# roadkill.net
KiCad netlist of a schematic drawn in EAGLE
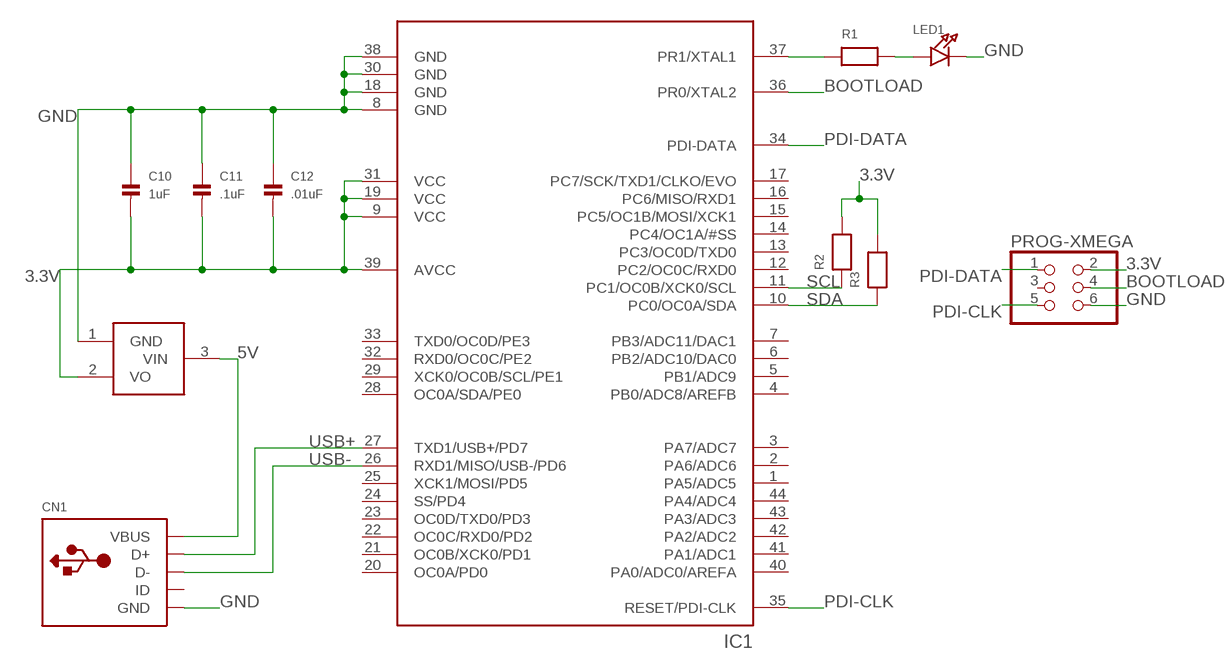
[diagram p0: schematic, sheet 1]
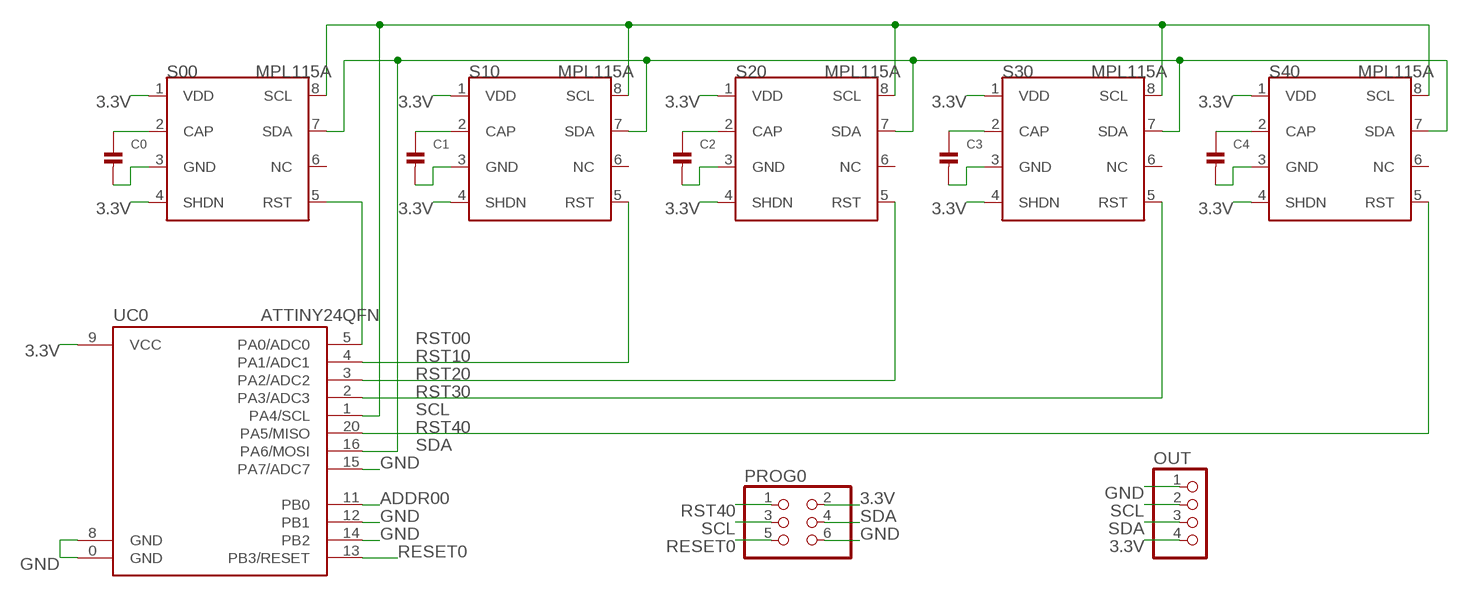
[diagram p1: schematic, sheet 2]
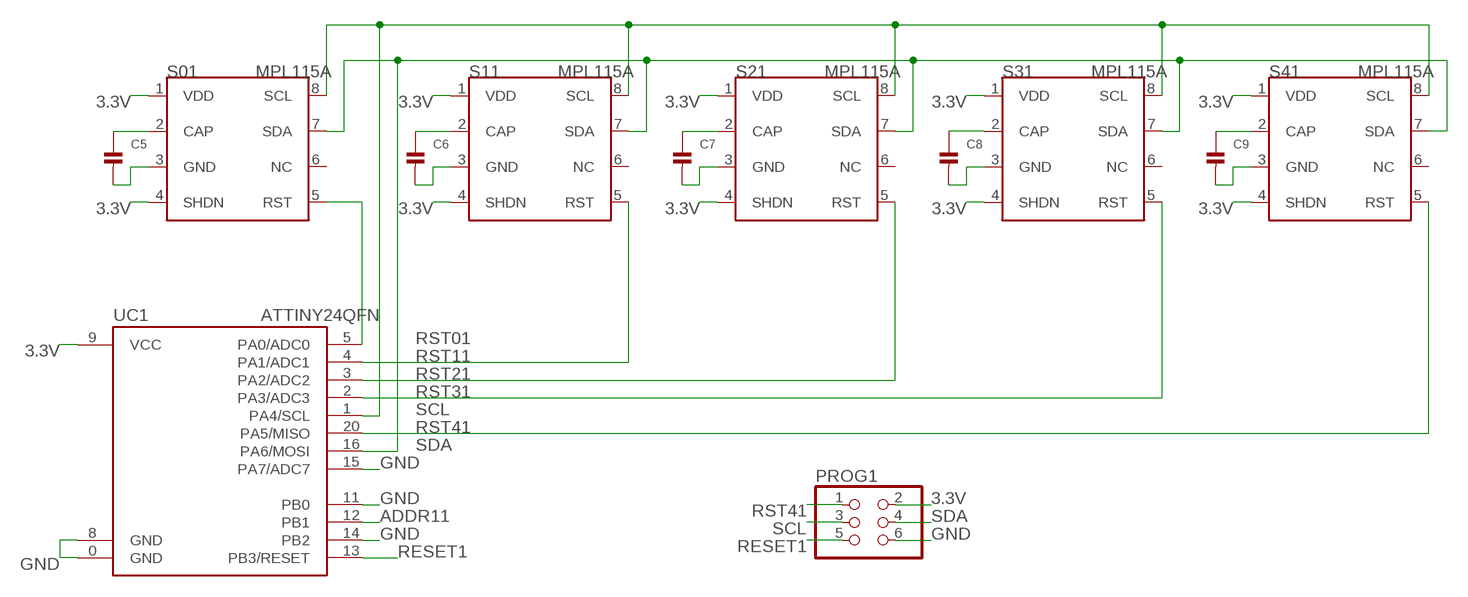
[diagram p2: schematic, sheet 3]
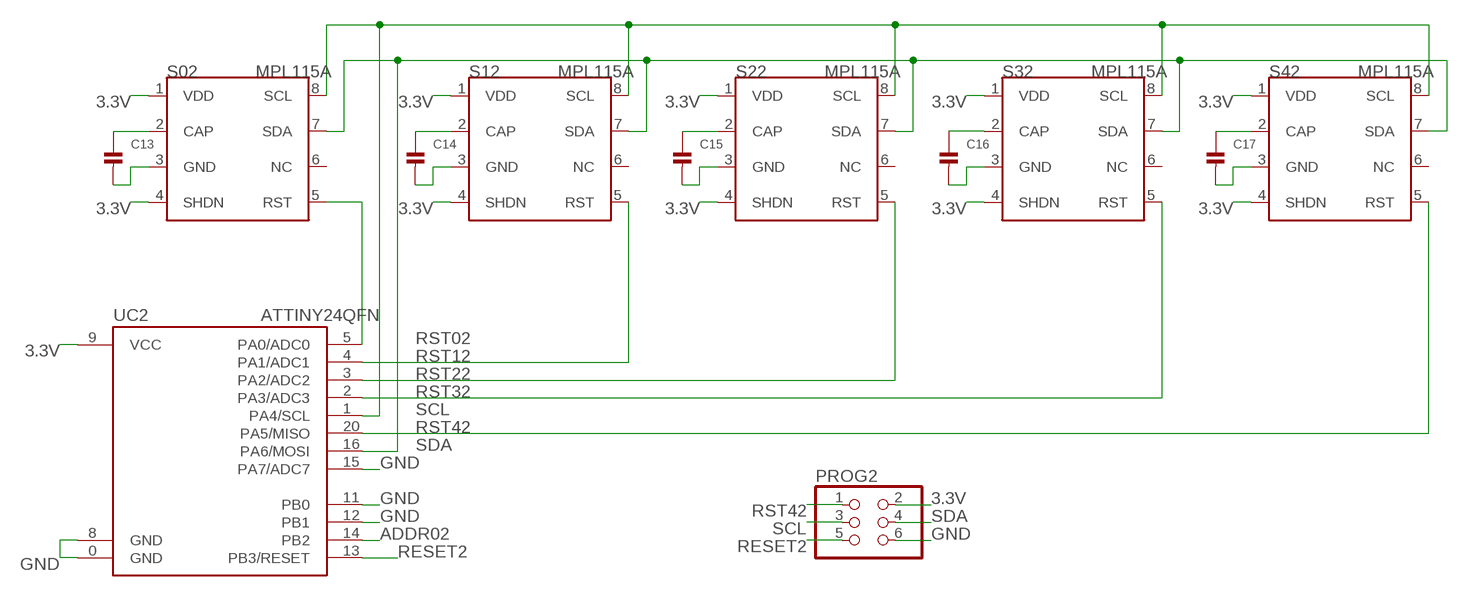
[diagram p3: schematic, sheet 4]
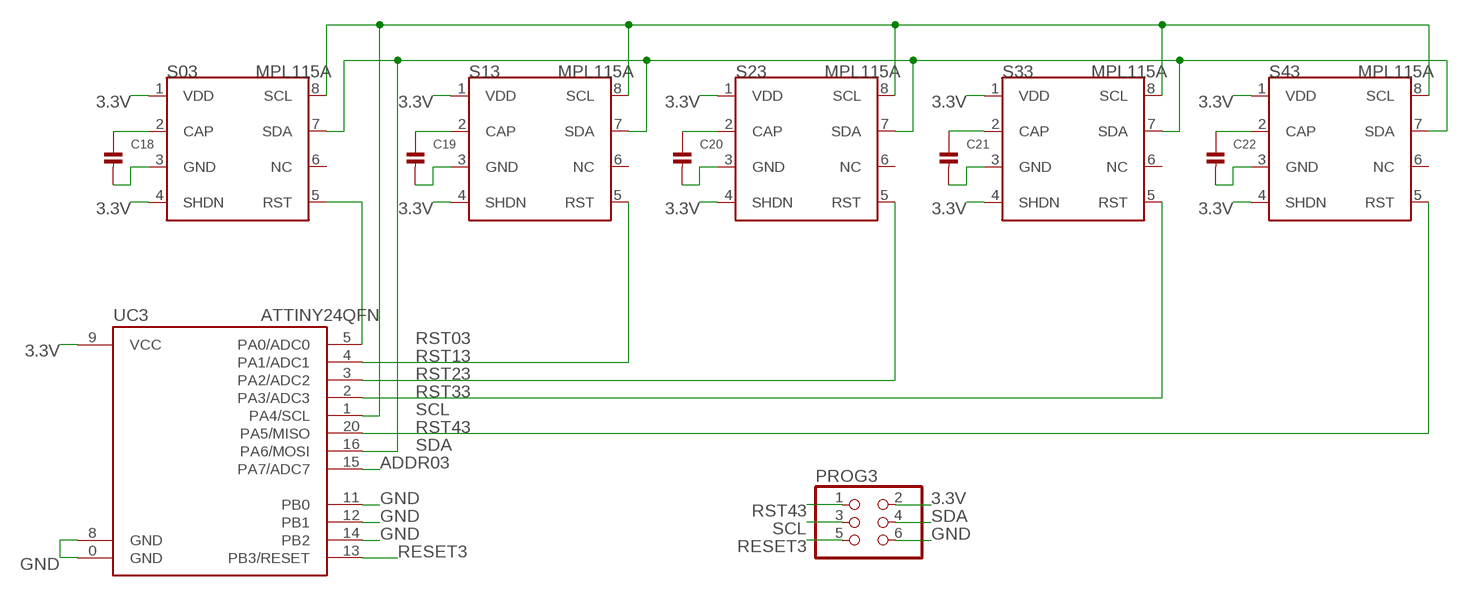
[diagram p4: schematic, sheet 5]

(export (version "E")
  (design (tool "Eeschema 10.0.6"))
  (components
    (comp (ref "C0")
      (value "CAP_CERAMIC0603")
      (footprint "eagle-import:0603")
      (libsource (lib "eagle-import") (part "CAP_CERAMIC0603"))
    )
    (comp (ref "C1")
      (value "CAP_CERAMIC0603")
      (footprint "eagle-import:0603")
      (libsource (lib "eagle-import") (part "CAP_CERAMIC0603"))
    )
    (comp (ref "C2")
      (value "CAP_CERAMIC0603")
      (footprint "eagle-import:0603")
      (libsource (lib "eagle-import") (part "CAP_CERAMIC0603"))
    )
    (comp (ref "C3")
      (value "CAP_CERAMIC0603")
      (footprint "eagle-import:0603")
      (libsource (lib "eagle-import") (part "CAP_CERAMIC0603"))
    )
    (comp (ref "C4")
      (value "CAP_CERAMIC0603")
      (footprint "eagle-import:0603")
      (libsource (lib "eagle-import") (part "CAP_CERAMIC0603"))
    )
    (comp (ref "OUT")
      (value "HEADER-1X4")
      (footprint "eagle-import:1X04_OVAL")
      (libsource (lib "eagle-import") (part "HEADER-1X4"))
    )
    (comp (ref "PROG0")
      (value "HEADER-2X3")
      (footprint "eagle-import:2X03")
      (libsource (lib "eagle-import") (part "HEADER-2X3"))
    )
    (comp (ref "S00")
      (value "MPL115A")
      (footprint "eagle-import:LGA-8")
      (libsource (lib "eagle-import") (part "MPL115A"))
    )
    (comp (ref "S10")
      (value "MPL115A")
      (footprint "eagle-import:LGA-8")
      (libsource (lib "eagle-import") (part "MPL115A"))
    )
    (comp (ref "S20")
      (value "MPL115A")
      (footprint "eagle-import:LGA-8")
      (libsource (lib "eagle-import") (part "MPL115A"))
    )
    (comp (ref "S30")
      (value "MPL115A")
      (footprint "eagle-import:LGA-8")
      (libsource (lib "eagle-import") (part "MPL115A"))
    )
    (comp (ref "S40")
      (value "MPL115A")
      (footprint "eagle-import:LGA-8")
      (libsource (lib "eagle-import") (part "MPL115A"))
    )
    (comp (ref "UC0")
      (value "ATTINY24QFN")
      (footprint "eagle-import:QFN20")
      (libsource (lib "eagle-import") (part "ATTINY24QFN"))
    )
    (comp (ref "C18")
      (value "CAP_CERAMIC0603")
      (footprint "eagle-import:0603")
      (libsource (lib "eagle-import") (part "CAP_CERAMIC0603"))
    )
    (comp (ref "C19")
      (value "CAP_CERAMIC0603")
      (footprint "eagle-import:0603")
      (libsource (lib "eagle-import") (part "CAP_CERAMIC0603"))
    )
    (comp (ref "C20")
      (value "CAP_CERAMIC0603")
      (footprint "eagle-import:0603")
      (libsource (lib "eagle-import") (part "CAP_CERAMIC0603"))
    )
    (comp (ref "C21")
      (value "CAP_CERAMIC0603")
      (footprint "eagle-import:0603")
      (libsource (lib "eagle-import") (part "CAP_CERAMIC0603"))
    )
    (comp (ref "C22")
      (value "CAP_CERAMIC0603")
      (footprint "eagle-import:0603")
      (libsource (lib "eagle-import") (part "CAP_CERAMIC0603"))
    )
    (comp (ref "PROG3")
      (value "HEADER-2X3")
      (footprint "eagle-import:2X03")
      (libsource (lib "eagle-import") (part "HEADER-2X3"))
    )
    (comp (ref "S03")
      (value "MPL115A")
      (footprint "eagle-import:LGA-8")
      (libsource (lib "eagle-import") (part "MPL115A"))
    )
    (comp (ref "S13")
      (value "MPL115A")
      (footprint "eagle-import:LGA-8")
      (libsource (lib "eagle-import") (part "MPL115A"))
    )
    (comp (ref "S23")
      (value "MPL115A")
      (footprint "eagle-import:LGA-8")
      (libsource (lib "eagle-import") (part "MPL115A"))
    )
    (comp (ref "S33")
      (value "MPL115A")
      (footprint "eagle-import:LGA-8")
      (libsource (lib "eagle-import") (part "MPL115A"))
    )
    (comp (ref "S43")
      (value "MPL115A")
      (footprint "eagle-import:LGA-8")
      (libsource (lib "eagle-import") (part "MPL115A"))
    )
    (comp (ref "UC3")
      (value "ATTINY24QFN")
      (footprint "eagle-import:QFN20")
      (libsource (lib "eagle-import") (part "ATTINY24QFN"))
    )
    (comp (ref "C5")
      (value "CAP_CERAMIC0603")
      (footprint "eagle-import:0603")
      (libsource (lib "eagle-import") (part "CAP_CERAMIC0603"))
    )
    (comp (ref "C6")
      (value "CAP_CERAMIC0603")
      (footprint "eagle-import:0603")
      (libsource (lib "eagle-import") (part "CAP_CERAMIC0603"))
    )
    (comp (ref "C7")
      (value "CAP_CERAMIC0603")
      (footprint "eagle-import:0603")
      (libsource (lib "eagle-import") (part "CAP_CERAMIC0603"))
    )
    (comp (ref "C8")
      (value "CAP_CERAMIC0603")
      (footprint "eagle-import:0603")
      (libsource (lib "eagle-import") (part "CAP_CERAMIC0603"))
    )
    (comp (ref "C9")
      (value "CAP_CERAMIC0603")
      (footprint "eagle-import:0603")
      (libsource (lib "eagle-import") (part "CAP_CERAMIC0603"))
    )
    (comp (ref "PROG1")
      (value "HEADER-2X3")
      (footprint "eagle-import:2X03")
      (libsource (lib "eagle-import") (part "HEADER-2X3"))
    )
    (comp (ref "S01")
      (value "MPL115A")
      (footprint "eagle-import:LGA-8")
      (libsource (lib "eagle-import") (part "MPL115A"))
    )
    (comp (ref "S11")
      (value "MPL115A")
      (footprint "eagle-import:LGA-8")
      (libsource (lib "eagle-import") (part "MPL115A"))
    )
    (comp (ref "S21")
      (value "MPL115A")
      (footprint "eagle-import:LGA-8")
      (libsource (lib "eagle-import") (part "MPL115A"))
    )
    (comp (ref "S31")
      (value "MPL115A")
      (footprint "eagle-import:LGA-8")
      (libsource (lib "eagle-import") (part "MPL115A"))
    )
    (comp (ref "S41")
      (value "MPL115A")
      (footprint "eagle-import:LGA-8")
      (libsource (lib "eagle-import") (part "MPL115A"))
    )
    (comp (ref "UC1")
      (value "ATTINY24QFN")
      (footprint "eagle-import:QFN20")
      (libsource (lib "eagle-import") (part "ATTINY24QFN"))
    )
    (comp (ref "C13")
      (value "CAP_CERAMIC0603")
      (footprint "eagle-import:0603")
      (libsource (lib "eagle-import") (part "CAP_CERAMIC0603"))
    )
    (comp (ref "C14")
      (value "CAP_CERAMIC0603")
      (footprint "eagle-import:0603")
      (libsource (lib "eagle-import") (part "CAP_CERAMIC0603"))
    )
    (comp (ref "C15")
      (value "CAP_CERAMIC0603")
      (footprint "eagle-import:0603")
      (libsource (lib "eagle-import") (part "CAP_CERAMIC0603"))
    )
    (comp (ref "C16")
      (value "CAP_CERAMIC0603")
      (footprint "eagle-import:0603")
      (libsource (lib "eagle-import") (part "CAP_CERAMIC0603"))
    )
    (comp (ref "C17")
      (value "CAP_CERAMIC0603")
      (footprint "eagle-import:0603")
      (libsource (lib "eagle-import") (part "CAP_CERAMIC0603"))
    )
    (comp (ref "PROG2")
      (value "HEADER-2X3")
      (footprint "eagle-import:2X03")
      (libsource (lib "eagle-import") (part "HEADER-2X3"))
    )
    (comp (ref "S02")
      (value "MPL115A")
      (footprint "eagle-import:LGA-8")
      (libsource (lib "eagle-import") (part "MPL115A"))
    )
    (comp (ref "S12")
      (value "MPL115A")
      (footprint "eagle-import:LGA-8")
      (libsource (lib "eagle-import") (part "MPL115A"))
    )
    (comp (ref "S22")
      (value "MPL115A")
      (footprint "eagle-import:LGA-8")
      (libsource (lib "eagle-import") (part "MPL115A"))
    )
    (comp (ref "S32")
      (value "MPL115A")
      (footprint "eagle-import:LGA-8")
      (libsource (lib "eagle-import") (part "MPL115A"))
    )
    (comp (ref "S42")
      (value "MPL115A")
      (footprint "eagle-import:LGA-8")
      (libsource (lib "eagle-import") (part "MPL115A"))
    )
    (comp (ref "UC2")
      (value "ATTINY24QFN")
      (footprint "eagle-import:QFN20")
      (libsource (lib "eagle-import") (part "ATTINY24QFN"))
    )
    (comp (ref "3.3V")
      (value "VREG")
      (footprint "eagle-import:SOT23-3")
      (libsource (lib "eagle-import") (part "VREG"))
    )
    (comp (ref "C10")
      (value "1uF")
      (footprint "eagle-import:0603")
      (libsource (lib "eagle-import") (part "CAP_CERAMIC0603"))
    )
    (comp (ref "C11")
      (value ".1uF")
      (footprint "eagle-import:0603")
      (libsource (lib "eagle-import") (part "CAP_CERAMIC0603"))
    )
    (comp (ref "C12")
      (value ".01uF")
      (footprint "eagle-import:0603")
      (libsource (lib "eagle-import") (part "CAP_CERAMIC0603"))
    )
    (comp (ref "CN1")
      (value "USBMINIB")
      (footprint "eagle-import:USB-MINIB")
      (libsource (lib "eagle-import") (part "USBMINIB"))
    )
    (comp (ref "IC1")
      (value "ATXMEGAXXA4U")
      (footprint "eagle-import:TQFP-44")
      (libsource (lib "eagle-import") (part "ATXMEGAXXA4U"))
    )
    (comp (ref "LED1")
      (value "LED0603")
      (footprint "eagle-import:CHIPLED_0603")
      (libsource (lib "eagle-import") (part "LED0603"))
    )
    (comp (ref "PROG-XMEGA")
      (value "HEADER-2X3")
      (footprint "eagle-import:2X03")
      (libsource (lib "eagle-import") (part "HEADER-2X3"))
    )
    (comp (ref "R1")
      (value "RESISTOR0603")
      (footprint "eagle-import:0603")
      (libsource (lib "eagle-import") (part "RESISTOR0603"))
    )
    (comp (ref "R2")
      (value "RESISTOR0603")
      (footprint "eagle-import:0603")
      (libsource (lib "eagle-import") (part "RESISTOR0603"))
    )
    (comp (ref "R3")
      (value "RESISTOR0603")
      (footprint "eagle-import:0603")
      (libsource (lib "eagle-import") (part "RESISTOR0603"))
    )
  )
  (nets
    (net (code "1") (name "3.3V") (class "Default")
      (node (ref "3.3V") (pin "2") (pinfunction "VO_2") (pintype "bidirectional"))
      (node (ref "C10") (pin "2") (pinfunction "P$2_2") (pintype "passive"))
      (node (ref "C11") (pin "2") (pinfunction "P$2_2") (pintype "passive"))
      (node (ref "C12") (pin "2") (pinfunction "P$2_2") (pintype "passive"))
      (node (ref "IC1") (pin "19") (pinfunction "VCC_19") (pintype "power_in"))
      (node (ref "IC1") (pin "31") (pinfunction "VCC_31") (pintype "power_in"))
      (node (ref "IC1") (pin "39") (pinfunction "AVCC_39") (pintype "power_in"))
      (node (ref "IC1") (pin "9") (pinfunction "VCC_9") (pintype "power_in"))
      (node (ref "OUT") (pin "4") (pinfunction "4_4") (pintype "passive"))
      (node (ref "PROG-XMEGA") (pin "2") (pinfunction "2_2") (pintype "passive"))
      (node (ref "PROG0") (pin "2") (pinfunction "2_2") (pintype "passive"))
      (node (ref "PROG1") (pin "2") (pinfunction "2_2") (pintype "passive"))
      (node (ref "PROG2") (pin "2") (pinfunction "2_2") (pintype "passive"))
      (node (ref "PROG3") (pin "2") (pinfunction "2_2") (pintype "passive"))
      (node (ref "R2") (pin "2") (pinfunction "2_2") (pintype "passive"))
      (node (ref "R3") (pin "2") (pinfunction "2_2") (pintype "passive"))
      (node (ref "S00") (pin "1") (pinfunction "VDD_1") (pintype "bidirectional"))
      (node (ref "S00") (pin "4") (pinfunction "SHDN_4") (pintype "bidirectional"))
      (node (ref "S01") (pin "1") (pinfunction "VDD_1") (pintype "bidirectional"))
      (node (ref "S01") (pin "4") (pinfunction "SHDN_4") (pintype "bidirectional"))
      (node (ref "S02") (pin "1") (pinfunction "VDD_1") (pintype "bidirectional"))
      (node (ref "S02") (pin "4") (pinfunction "SHDN_4") (pintype "bidirectional"))
      (node (ref "S03") (pin "1") (pinfunction "VDD_1") (pintype "bidirectional"))
      (node (ref "S03") (pin "4") (pinfunction "SHDN_4") (pintype "bidirectional"))
      (node (ref "S10") (pin "1") (pinfunction "VDD_1") (pintype "bidirectional"))
      (node (ref "S10") (pin "4") (pinfunction "SHDN_4") (pintype "bidirectional"))
      (node (ref "S11") (pin "1") (pinfunction "VDD_1") (pintype "bidirectional"))
      (node (ref "S11") (pin "4") (pinfunction "SHDN_4") (pintype "bidirectional"))
      (node (ref "S12") (pin "1") (pinfunction "VDD_1") (pintype "bidirectional"))
      (node (ref "S12") (pin "4") (pinfunction "SHDN_4") (pintype "bidirectional"))
      (node (ref "S13") (pin "1") (pinfunction "VDD_1") (pintype "bidirectional"))
      (node (ref "S13") (pin "4") (pinfunction "SHDN_4") (pintype "bidirectional"))
      (node (ref "S20") (pin "1") (pinfunction "VDD_1") (pintype "bidirectional"))
      (node (ref "S20") (pin "4") (pinfunction "SHDN_4") (pintype "bidirectional"))
      (node (ref "S21") (pin "1") (pinfunction "VDD_1") (pintype "bidirectional"))
      (node (ref "S21") (pin "4") (pinfunction "SHDN_4") (pintype "bidirectional"))
      (node (ref "S22") (pin "1") (pinfunction "VDD_1") (pintype "bidirectional"))
      (node (ref "S22") (pin "4") (pinfunction "SHDN_4") (pintype "bidirectional"))
      (node (ref "S23") (pin "1") (pinfunction "VDD_1") (pintype "bidirectional"))
      (node (ref "S23") (pin "4") (pinfunction "SHDN_4") (pintype "bidirectional"))
      (node (ref "S30") (pin "1") (pinfunction "VDD_1") (pintype "bidirectional"))
      (node (ref "S30") (pin "4") (pinfunction "SHDN_4") (pintype "bidirectional"))
      (node (ref "S31") (pin "1") (pinfunction "VDD_1") (pintype "bidirectional"))
      (node (ref "S31") (pin "4") (pinfunction "SHDN_4") (pintype "bidirectional"))
      (node (ref "S32") (pin "1") (pinfunction "VDD_1") (pintype "bidirectional"))
      (node (ref "S32") (pin "4") (pinfunction "SHDN_4") (pintype "bidirectional"))
      (node (ref "S33") (pin "1") (pinfunction "VDD_1") (pintype "bidirectional"))
      (node (ref "S33") (pin "4") (pinfunction "SHDN_4") (pintype "bidirectional"))
      (node (ref "S40") (pin "1") (pinfunction "VDD_1") (pintype "bidirectional"))
      (node (ref "S40") (pin "4") (pinfunction "SHDN_4") (pintype "bidirectional"))
      (node (ref "S41") (pin "1") (pinfunction "VDD_1") (pintype "bidirectional"))
      (node (ref "S41") (pin "4") (pinfunction "SHDN_4") (pintype "bidirectional"))
      (node (ref "S42") (pin "1") (pinfunction "VDD_1") (pintype "bidirectional"))
      (node (ref "S42") (pin "4") (pinfunction "SHDN_4") (pintype "bidirectional"))
      (node (ref "S43") (pin "1") (pinfunction "VDD_1") (pintype "bidirectional"))
      (node (ref "S43") (pin "4") (pinfunction "SHDN_4") (pintype "bidirectional"))
      (node (ref "UC0") (pin "9") (pinfunction "VCC_9") (pintype "bidirectional"))
      (node (ref "UC1") (pin "9") (pinfunction "VCC_9") (pintype "bidirectional"))
      (node (ref "UC2") (pin "9") (pinfunction "VCC_9") (pintype "bidirectional"))
      (node (ref "UC3") (pin "9") (pinfunction "VCC_9") (pintype "bidirectional"))
    )
    (net (code "2") (name "5V") (class "Default")
      (node (ref "3.3V") (pin "3") (pinfunction "VIN_3") (pintype "bidirectional"))
      (node (ref "CN1") (pin "VBUS") (pinfunction "VBUS_VBUS") (pintype "power_in"))
    )
    (net (code "3") (name "ADDR00") (class "Default")
      (node (ref "UC0") (pin "11") (pinfunction "PB0_11") (pintype "bidirectional"))
    )
    (net (code "4") (name "ADDR02") (class "Default")
      (node (ref "UC2") (pin "14") (pinfunction "PB2_14") (pintype "bidirectional"))
    )
    (net (code "5") (name "ADDR03") (class "Default")
      (node (ref "UC3") (pin "15") (pinfunction "PA7/ADC7_15") (pintype "bidirectional"))
    )
    (net (code "6") (name "ADDR11") (class "Default")
      (node (ref "UC1") (pin "12") (pinfunction "PB1_12") (pintype "bidirectional"))
    )
    (net (code "7") (name "BOOTLOAD") (class "Default")
      (node (ref "IC1") (pin "36") (pinfunction "PR0/XTAL2_36") (pintype "bidirectional"))
      (node (ref "PROG-XMEGA") (pin "4") (pinfunction "4_4") (pintype "passive"))
    )
    (net (code "8") (name "GND") (class "Default")
      (node (ref "3.3V") (pin "1") (pinfunction "GND_1") (pintype "bidirectional"))
      (node (ref "C0") (pin "2") (pinfunction "P$2_2") (pintype "passive"))
      (node (ref "C1") (pin "2") (pinfunction "P$2_2") (pintype "passive"))
      (node (ref "C10") (pin "1") (pinfunction "P$1_1") (pintype "passive"))
      (node (ref "C11") (pin "1") (pinfunction "P$1_1") (pintype "passive"))
      (node (ref "C12") (pin "1") (pinfunction "P$1_1") (pintype "passive"))
      (node (ref "C13") (pin "2") (pinfunction "P$2_2") (pintype "passive"))
      (node (ref "C14") (pin "2") (pinfunction "P$2_2") (pintype "passive"))
      (node (ref "C15") (pin "2") (pinfunction "P$2_2") (pintype "passive"))
      (node (ref "C16") (pin "2") (pinfunction "P$2_2") (pintype "passive"))
      (node (ref "C17") (pin "2") (pinfunction "P$2_2") (pintype "passive"))
      (node (ref "C18") (pin "2") (pinfunction "P$2_2") (pintype "passive"))
      (node (ref "C19") (pin "2") (pinfunction "P$2_2") (pintype "passive"))
      (node (ref "C2") (pin "2") (pinfunction "P$2_2") (pintype "passive"))
      (node (ref "C20") (pin "2") (pinfunction "P$2_2") (pintype "passive"))
      (node (ref "C21") (pin "2") (pinfunction "P$2_2") (pintype "passive"))
      (node (ref "C22") (pin "2") (pinfunction "P$2_2") (pintype "passive"))
      (node (ref "C3") (pin "2") (pinfunction "P$2_2") (pintype "passive"))
      (node (ref "C4") (pin "2") (pinfunction "P$2_2") (pintype "passive"))
      (node (ref "C5") (pin "2") (pinfunction "P$2_2") (pintype "passive"))
      (node (ref "C6") (pin "2") (pinfunction "P$2_2") (pintype "passive"))
      (node (ref "C7") (pin "2") (pinfunction "P$2_2") (pintype "passive"))
      (node (ref "C8") (pin "2") (pinfunction "P$2_2") (pintype "passive"))
      (node (ref "C9") (pin "2") (pinfunction "P$2_2") (pintype "passive"))
      (node (ref "CN1") (pin "GND") (pinfunction "GND_GND") (pintype "power_in"))
      (node (ref "IC1") (pin "18") (pinfunction "GND_18") (pintype "power_in"))
      (node (ref "IC1") (pin "30") (pinfunction "GND_30") (pintype "power_in"))
      (node (ref "IC1") (pin "38") (pinfunction "GND_38") (pintype "power_in"))
      (node (ref "IC1") (pin "8") (pinfunction "GND_8") (pintype "power_in"))
      (node (ref "LED1") (pin "C") (pinfunction "C_C") (pintype "passive"))
      (node (ref "OUT") (pin "1") (pinfunction "1_1") (pintype "passive"))
      (node (ref "PROG-XMEGA") (pin "6") (pinfunction "6_6") (pintype "passive"))
      (node (ref "PROG0") (pin "6") (pinfunction "6_6") (pintype "passive"))
      (node (ref "PROG1") (pin "6") (pinfunction "6_6") (pintype "passive"))
      (node (ref "PROG2") (pin "6") (pinfunction "6_6") (pintype "passive"))
      (node (ref "PROG3") (pin "6") (pinfunction "6_6") (pintype "passive"))
      (node (ref "S00") (pin "3") (pinfunction "GND_3") (pintype "bidirectional"))
      (node (ref "S01") (pin "3") (pinfunction "GND_3") (pintype "bidirectional"))
      (node (ref "S02") (pin "3") (pinfunction "GND_3") (pintype "bidirectional"))
      (node (ref "S03") (pin "3") (pinfunction "GND_3") (pintype "bidirectional"))
      (node (ref "S10") (pin "3") (pinfunction "GND_3") (pintype "bidirectional"))
      (node (ref "S11") (pin "3") (pinfunction "GND_3") (pintype "bidirectional"))
      (node (ref "S12") (pin "3") (pinfunction "GND_3") (pintype "bidirectional"))
      (node (ref "S13") (pin "3") (pinfunction "GND_3") (pintype "bidirectional"))
      (node (ref "S20") (pin "3") (pinfunction "GND_3") (pintype "bidirectional"))
      (node (ref "S21") (pin "3") (pinfunction "GND_3") (pintype "bidirectional"))
      (node (ref "S22") (pin "3") (pinfunction "GND_3") (pintype "bidirectional"))
      (node (ref "S23") (pin "3") (pinfunction "GND_3") (pintype "bidirectional"))
      (node (ref "S30") (pin "3") (pinfunction "GND_3") (pintype "bidirectional"))
      (node (ref "S31") (pin "3") (pinfunction "GND_3") (pintype "bidirectional"))
      (node (ref "S32") (pin "3") (pinfunction "GND_3") (pintype "bidirectional"))
      (node (ref "S33") (pin "3") (pinfunction "GND_3") (pintype "bidirectional"))
      (node (ref "S40") (pin "3") (pinfunction "GND_3") (pintype "bidirectional"))
      (node (ref "S41") (pin "3") (pinfunction "GND_3") (pintype "bidirectional"))
      (node (ref "S42") (pin "3") (pinfunction "GND_3") (pintype "bidirectional"))
      (node (ref "S43") (pin "3") (pinfunction "GND_3") (pintype "bidirectional"))
      (node (ref "UC0") (pin "0") (pinfunction "GND_0") (pintype "bidirectional"))
      (node (ref "UC0") (pin "12") (pinfunction "PB1_12") (pintype "bidirectional"))
      (node (ref "UC0") (pin "14") (pinfunction "PB2_14") (pintype "bidirectional"))
      (node (ref "UC0") (pin "15") (pinfunction "PA7/ADC7_15") (pintype "bidirectional"))
      (node (ref "UC0") (pin "8") (pinfunction "GND_8") (pintype "bidirectional"))
      (node (ref "UC1") (pin "0") (pinfunction "GND_0") (pintype "bidirectional"))
      (node (ref "UC1") (pin "11") (pinfunction "PB0_11") (pintype "bidirectional"))
      (node (ref "UC1") (pin "14") (pinfunction "PB2_14") (pintype "bidirectional"))
      (node (ref "UC1") (pin "15") (pinfunction "PA7/ADC7_15") (pintype "bidirectional"))
      (node (ref "UC1") (pin "8") (pinfunction "GND_8") (pintype "bidirectional"))
      (node (ref "UC2") (pin "0") (pinfunction "GND_0") (pintype "bidirectional"))
      (node (ref "UC2") (pin "11") (pinfunction "PB0_11") (pintype "bidirectional"))
      (node (ref "UC2") (pin "12") (pinfunction "PB1_12") (pintype "bidirectional"))
      (node (ref "UC2") (pin "15") (pinfunction "PA7/ADC7_15") (pintype "bidirectional"))
      (node (ref "UC2") (pin "8") (pinfunction "GND_8") (pintype "bidirectional"))
      (node (ref "UC3") (pin "0") (pinfunction "GND_0") (pintype "bidirectional"))
      (node (ref "UC3") (pin "11") (pinfunction "PB0_11") (pintype "bidirectional"))
      (node (ref "UC3") (pin "12") (pinfunction "PB1_12") (pintype "bidirectional"))
      (node (ref "UC3") (pin "14") (pinfunction "PB2_14") (pintype "bidirectional"))
      (node (ref "UC3") (pin "8") (pinfunction "GND_8") (pintype "bidirectional"))
    )
    (net (code "9") (name "Net-(C0-P$1)") (class "Default")
      (node (ref "C0") (pin "1") (pinfunction "P$1_1") (pintype "passive"))
      (node (ref "S00") (pin "2") (pinfunction "CAP_2") (pintype "bidirectional"))
    )
    (net (code "10") (name "Net-(C1-P$1)") (class "Default")
      (node (ref "C1") (pin "1") (pinfunction "P$1_1") (pintype "passive"))
      (node (ref "S10") (pin "2") (pinfunction "CAP_2") (pintype "bidirectional"))
    )
    (net (code "11") (name "Net-(C2-P$1)") (class "Default")
      (node (ref "C2") (pin "1") (pinfunction "P$1_1") (pintype "passive"))
      (node (ref "S20") (pin "2") (pinfunction "CAP_2") (pintype "bidirectional"))
    )
    (net (code "12") (name "Net-(C3-P$1)") (class "Default")
      (node (ref "C3") (pin "1") (pinfunction "P$1_1") (pintype "passive"))
      (node (ref "S30") (pin "2") (pinfunction "CAP_2") (pintype "bidirectional"))
    )
    (net (code "13") (name "Net-(C4-P$1)") (class "Default")
      (node (ref "C4") (pin "1") (pinfunction "P$1_1") (pintype "passive"))
      (node (ref "S40") (pin "2") (pinfunction "CAP_2") (pintype "bidirectional"))
    )
    (net (code "14") (name "Net-(C5-P$1)") (class "Default")
      (node (ref "C5") (pin "1") (pinfunction "P$1_1") (pintype "passive"))
      (node (ref "S01") (pin "2") (pinfunction "CAP_2") (pintype "bidirectional"))
    )
    (net (code "15") (name "Net-(C6-P$1)") (class "Default")
      (node (ref "C6") (pin "1") (pinfunction "P$1_1") (pintype "passive"))
      (node (ref "S11") (pin "2") (pinfunction "CAP_2") (pintype "bidirectional"))
    )
    (net (code "16") (name "Net-(C7-P$1)") (class "Default")
      (node (ref "C7") (pin "1") (pinfunction "P$1_1") (pintype "passive"))
      (node (ref "S21") (pin "2") (pinfunction "CAP_2") (pintype "bidirectional"))
    )
    (net (code "17") (name "Net-(C8-P$1)") (class "Default")
      (node (ref "C8") (pin "1") (pinfunction "P$1_1") (pintype "passive"))
      (node (ref "S31") (pin "2") (pinfunction "CAP_2") (pintype "bidirectional"))
    )
    (net (code "18") (name "Net-(C9-P$1)") (class "Default")
      (node (ref "C9") (pin "1") (pinfunction "P$1_1") (pintype "passive"))
      (node (ref "S41") (pin "2") (pinfunction "CAP_2") (pintype "bidirectional"))
    )
    (net (code "19") (name "Net-(C13-P$1)") (class "Default")
      (node (ref "C13") (pin "1") (pinfunction "P$1_1") (pintype "passive"))
      (node (ref "S02") (pin "2") (pinfunction "CAP_2") (pintype "bidirectional"))
    )
    (net (code "20") (name "Net-(C14-P$1)") (class "Default")
      (node (ref "C14") (pin "1") (pinfunction "P$1_1") (pintype "passive"))
      (node (ref "S12") (pin "2") (pinfunction "CAP_2") (pintype "bidirectional"))
    )
    (net (code "21") (name "Net-(C15-P$1)") (class "Default")
      (node (ref "C15") (pin "1") (pinfunction "P$1_1") (pintype "passive"))
      (node (ref "S22") (pin "2") (pinfunction "CAP_2") (pintype "bidirectional"))
    )
    (net (code "22") (name "Net-(C16-P$1)") (class "Default")
      (node (ref "C16") (pin "1") (pinfunction "P$1_1") (pintype "passive"))
      (node (ref "S32") (pin "2") (pinfunction "CAP_2") (pintype "bidirectional"))
    )
    (net (code "23") (name "Net-(C17-P$1)") (class "Default")
      (node (ref "C17") (pin "1") (pinfunction "P$1_1") (pintype "passive"))
      (node (ref "S42") (pin "2") (pinfunction "CAP_2") (pintype "bidirectional"))
    )
    (net (code "24") (name "Net-(C18-P$1)") (class "Default")
      (node (ref "C18") (pin "1") (pinfunction "P$1_1") (pintype "passive"))
      (node (ref "S03") (pin "2") (pinfunction "CAP_2") (pintype "bidirectional"))
    )
    (net (code "25") (name "Net-(C19-P$1)") (class "Default")
      (node (ref "C19") (pin "1") (pinfunction "P$1_1") (pintype "passive"))
      (node (ref "S13") (pin "2") (pinfunction "CAP_2") (pintype "bidirectional"))
    )
    (net (code "26") (name "Net-(C20-P$1)") (class "Default")
      (node (ref "C20") (pin "1") (pinfunction "P$1_1") (pintype "passive"))
      (node (ref "S23") (pin "2") (pinfunction "CAP_2") (pintype "bidirectional"))
    )
    (net (code "27") (name "Net-(C21-P$1)") (class "Default")
      (node (ref "C21") (pin "1") (pinfunction "P$1_1") (pintype "passive"))
      (node (ref "S33") (pin "2") (pinfunction "CAP_2") (pintype "bidirectional"))
    )
    (net (code "28") (name "Net-(C22-P$1)") (class "Default")
      (node (ref "C22") (pin "1") (pinfunction "P$1_1") (pintype "passive"))
      (node (ref "S43") (pin "2") (pinfunction "CAP_2") (pintype "bidirectional"))
    )
    (net (code "29") (name "Net-(IC1-PR1{slash}XTAL1)") (class "Default")
      (node (ref "IC1") (pin "37") (pinfunction "PR1/XTAL1_37") (pintype "bidirectional"))
      (node (ref "R1") (pin "1") (pinfunction "1_1") (pintype "passive"))
    )
    (net (code "30") (name "Net-(LED1-PadA)") (class "Default")
      (node (ref "LED1") (pin "A") (pinfunction "A_A") (pintype "passive"))
      (node (ref "R1") (pin "2") (pinfunction "2_2") (pintype "passive"))
    )
    (net (code "31") (name "PDI-CLK") (class "Default")
      (node (ref "IC1") (pin "35") (pinfunction "RESET/PDI-CLK_35") (pintype "input"))
      (node (ref "PROG-XMEGA") (pin "5") (pinfunction "5_5") (pintype "passive"))
    )
    (net (code "32") (name "PDI-DATA") (class "Default")
      (node (ref "IC1") (pin "34") (pinfunction "PDI-DATA_34") (pintype "bidirectional"))
      (node (ref "PROG-XMEGA") (pin "1") (pinfunction "1_1") (pintype "passive"))
    )
    (net (code "33") (name "RESET0") (class "Default")
      (node (ref "PROG0") (pin "5") (pinfunction "5_5") (pintype "passive"))
      (node (ref "UC0") (pin "13") (pinfunction "PB3/RESET_13") (pintype "bidirectional"))
    )
    (net (code "34") (name "RESET1") (class "Default")
      (node (ref "PROG1") (pin "5") (pinfunction "5_5") (pintype "passive"))
      (node (ref "UC1") (pin "13") (pinfunction "PB3/RESET_13") (pintype "bidirectional"))
    )
    (net (code "35") (name "RESET2") (class "Default")
      (node (ref "PROG2") (pin "5") (pinfunction "5_5") (pintype "passive"))
      (node (ref "UC2") (pin "13") (pinfunction "PB3/RESET_13") (pintype "bidirectional"))
    )
    (net (code "36") (name "RESET3") (class "Default")
      (node (ref "PROG3") (pin "5") (pinfunction "5_5") (pintype "passive"))
      (node (ref "UC3") (pin "13") (pinfunction "PB3/RESET_13") (pintype "bidirectional"))
    )
    (net (code "37") (name "RST00") (class "Default")
      (node (ref "S00") (pin "5") (pinfunction "RST_5") (pintype "bidirectional"))
      (node (ref "UC0") (pin "5") (pinfunction "PA0/ADC0_5") (pintype "bidirectional"))
    )
    (net (code "38") (name "RST01") (class "Default")
      (node (ref "S01") (pin "5") (pinfunction "RST_5") (pintype "bidirectional"))
      (node (ref "UC1") (pin "5") (pinfunction "PA0/ADC0_5") (pintype "bidirectional"))
    )
    (net (code "39") (name "RST02") (class "Default")
      (node (ref "S02") (pin "5") (pinfunction "RST_5") (pintype "bidirectional"))
      (node (ref "UC2") (pin "5") (pinfunction "PA0/ADC0_5") (pintype "bidirectional"))
    )
    (net (code "40") (name "RST03") (class "Default")
      (node (ref "S03") (pin "5") (pinfunction "RST_5") (pintype "bidirectional"))
      (node (ref "UC3") (pin "5") (pinfunction "PA0/ADC0_5") (pintype "bidirectional"))
    )
    (net (code "41") (name "RST10") (class "Default")
      (node (ref "S10") (pin "5") (pinfunction "RST_5") (pintype "bidirectional"))
      (node (ref "UC0") (pin "4") (pinfunction "PA1/ADC1_4") (pintype "bidirectional"))
    )
    (net (code "42") (name "RST11") (class "Default")
      (node (ref "S11") (pin "5") (pinfunction "RST_5") (pintype "bidirectional"))
      (node (ref "UC1") (pin "4") (pinfunction "PA1/ADC1_4") (pintype "bidirectional"))
    )
    (net (code "43") (name "RST12") (class "Default")
      (node (ref "S12") (pin "5") (pinfunction "RST_5") (pintype "bidirectional"))
      (node (ref "UC2") (pin "4") (pinfunction "PA1/ADC1_4") (pintype "bidirectional"))
    )
    (net (code "44") (name "RST13") (class "Default")
      (node (ref "S13") (pin "5") (pinfunction "RST_5") (pintype "bidirectional"))
      (node (ref "UC3") (pin "4") (pinfunction "PA1/ADC1_4") (pintype "bidirectional"))
    )
    (net (code "45") (name "RST20") (class "Default")
      (node (ref "S20") (pin "5") (pinfunction "RST_5") (pintype "bidirectional"))
      (node (ref "UC0") (pin "3") (pinfunction "PA2/ADC2_3") (pintype "bidirectional"))
    )
    (net (code "46") (name "RST21") (class "Default")
      (node (ref "S21") (pin "5") (pinfunction "RST_5") (pintype "bidirectional"))
      (node (ref "UC1") (pin "3") (pinfunction "PA2/ADC2_3") (pintype "bidirectional"))
    )
    (net (code "47") (name "RST22") (class "Default")
      (node (ref "S22") (pin "5") (pinfunction "RST_5") (pintype "bidirectional"))
      (node (ref "UC2") (pin "3") (pinfunction "PA2/ADC2_3") (pintype "bidirectional"))
    )
    (net (code "48") (name "RST23") (class "Default")
      (node (ref "S23") (pin "5") (pinfunction "RST_5") (pintype "bidirectional"))
      (node (ref "UC3") (pin "3") (pinfunction "PA2/ADC2_3") (pintype "bidirectional"))
    )
    (net (code "49") (name "RST30") (class "Default")
      (node (ref "S30") (pin "5") (pinfunction "RST_5") (pintype "bidirectional"))
      (node (ref "UC0") (pin "2") (pinfunction "PA3/ADC3_2") (pintype "bidirectional"))
    )
    (net (code "50") (name "RST31") (class "Default")
      (node (ref "S31") (pin "5") (pinfunction "RST_5") (pintype "bidirectional"))
      (node (ref "UC1") (pin "2") (pinfunction "PA3/ADC3_2") (pintype "bidirectional"))
    )
    (net (code "51") (name "RST32") (class "Default")
      (node (ref "S32") (pin "5") (pinfunction "RST_5") (pintype "bidirectional"))
      (node (ref "UC2") (pin "2") (pinfunction "PA3/ADC3_2") (pintype "bidirectional"))
    )
    (net (code "52") (name "RST33") (class "Default")
      (node (ref "S33") (pin "5") (pinfunction "RST_5") (pintype "bidirectional"))
      (node (ref "UC3") (pin "2") (pinfunction "PA3/ADC3_2") (pintype "bidirectional"))
    )
    (net (code "53") (name "RST40") (class "Default")
      (node (ref "PROG0") (pin "1") (pinfunction "1_1") (pintype "passive"))
      (node (ref "S40") (pin "5") (pinfunction "RST_5") (pintype "bidirectional"))
      (node (ref "UC0") (pin "20") (pinfunction "PA5/MISO_20") (pintype "bidirectional"))
    )
    (net (code "54") (name "RST41") (class "Default")
      (node (ref "PROG1") (pin "1") (pinfunction "1_1") (pintype "passive"))
      (node (ref "S41") (pin "5") (pinfunction "RST_5") (pintype "bidirectional"))
      (node (ref "UC1") (pin "20") (pinfunction "PA5/MISO_20") (pintype "bidirectional"))
    )
    (net (code "55") (name "RST42") (class "Default")
      (node (ref "PROG2") (pin "1") (pinfunction "1_1") (pintype "passive"))
      (node (ref "S42") (pin "5") (pinfunction "RST_5") (pintype "bidirectional"))
      (node (ref "UC2") (pin "20") (pinfunction "PA5/MISO_20") (pintype "bidirectional"))
    )
    (net (code "56") (name "RST43") (class "Default")
      (node (ref "PROG3") (pin "1") (pinfunction "1_1") (pintype "passive"))
      (node (ref "S43") (pin "5") (pinfunction "RST_5") (pintype "bidirectional"))
      (node (ref "UC3") (pin "20") (pinfunction "PA5/MISO_20") (pintype "bidirectional"))
    )
    (net (code "57") (name "SCL") (class "Default")
      (node (ref "IC1") (pin "11") (pinfunction "PC1/OC0B/XCK0/SCL_11") (pintype "bidirectional"))
      (node (ref "OUT") (pin "2") (pinfunction "2_2") (pintype "passive"))
      (node (ref "PROG0") (pin "3") (pinfunction "3_3") (pintype "passive"))
      (node (ref "PROG1") (pin "3") (pinfunction "3_3") (pintype "passive"))
      (node (ref "PROG2") (pin "3") (pinfunction "3_3") (pintype "passive"))
      (node (ref "PROG3") (pin "3") (pinfunction "3_3") (pintype "passive"))
      (node (ref "R2") (pin "1") (pinfunction "1_1") (pintype "passive"))
      (node (ref "S00") (pin "8") (pinfunction "SCL_8") (pintype "bidirectional"))
      (node (ref "S01") (pin "8") (pinfunction "SCL_8") (pintype "bidirectional"))
      (node (ref "S02") (pin "8") (pinfunction "SCL_8") (pintype "bidirectional"))
      (node (ref "S03") (pin "8") (pinfunction "SCL_8") (pintype "bidirectional"))
      (node (ref "S10") (pin "8") (pinfunction "SCL_8") (pintype "bidirectional"))
      (node (ref "S11") (pin "8") (pinfunction "SCL_8") (pintype "bidirectional"))
      (node (ref "S12") (pin "8") (pinfunction "SCL_8") (pintype "bidirectional"))
      (node (ref "S13") (pin "8") (pinfunction "SCL_8") (pintype "bidirectional"))
      (node (ref "S20") (pin "8") (pinfunction "SCL_8") (pintype "bidirectional"))
      (node (ref "S21") (pin "8") (pinfunction "SCL_8") (pintype "bidirectional"))
      (node (ref "S22") (pin "8") (pinfunction "SCL_8") (pintype "bidirectional"))
      (node (ref "S23") (pin "8") (pinfunction "SCL_8") (pintype "bidirectional"))
      (node (ref "S30") (pin "8") (pinfunction "SCL_8") (pintype "bidirectional"))
      (node (ref "S31") (pin "8") (pinfunction "SCL_8") (pintype "bidirectional"))
      (node (ref "S32") (pin "8") (pinfunction "SCL_8") (pintype "bidirectional"))
      (node (ref "S33") (pin "8") (pinfunction "SCL_8") (pintype "bidirectional"))
      (node (ref "S40") (pin "8") (pinfunction "SCL_8") (pintype "bidirectional"))
      (node (ref "S41") (pin "8") (pinfunction "SCL_8") (pintype "bidirectional"))
      (node (ref "S42") (pin "8") (pinfunction "SCL_8") (pintype "bidirectional"))
      (node (ref "S43") (pin "8") (pinfunction "SCL_8") (pintype "bidirectional"))
      (node (ref "UC0") (pin "1") (pinfunction "PA4/SCL_1") (pintype "bidirectional"))
      (node (ref "UC1") (pin "1") (pinfunction "PA4/SCL_1") (pintype "bidirectional"))
      (node (ref "UC2") (pin "1") (pinfunction "PA4/SCL_1") (pintype "bidirectional"))
      (node (ref "UC3") (pin "1") (pinfunction "PA4/SCL_1") (pintype "bidirectional"))
    )
    (net (code "58") (name "SDA") (class "Default")
      (node (ref "IC1") (pin "10") (pinfunction "PC0/OC0A/SDA_10") (pintype "bidirectional"))
      (node (ref "OUT") (pin "3") (pinfunction "3_3") (pintype "passive"))
      (node (ref "PROG0") (pin "4") (pinfunction "4_4") (pintype "passive"))
      (node (ref "PROG1") (pin "4") (pinfunction "4_4") (pintype "passive"))
      (node (ref "PROG2") (pin "4") (pinfunction "4_4") (pintype "passive"))
      (node (ref "PROG3") (pin "4") (pinfunction "4_4") (pintype "passive"))
      (node (ref "R3") (pin "1") (pinfunction "1_1") (pintype "passive"))
      (node (ref "S00") (pin "7") (pinfunction "SDA_7") (pintype "bidirectional"))
      (node (ref "S01") (pin "7") (pinfunction "SDA_7") (pintype "bidirectional"))
      (node (ref "S02") (pin "7") (pinfunction "SDA_7") (pintype "bidirectional"))
      (node (ref "S03") (pin "7") (pinfunction "SDA_7") (pintype "bidirectional"))
      (node (ref "S10") (pin "7") (pinfunction "SDA_7") (pintype "bidirectional"))
      (node (ref "S11") (pin "7") (pinfunction "SDA_7") (pintype "bidirectional"))
      (node (ref "S12") (pin "7") (pinfunction "SDA_7") (pintype "bidirectional"))
      (node (ref "S13") (pin "7") (pinfunction "SDA_7") (pintype "bidirectional"))
      (node (ref "S20") (pin "7") (pinfunction "SDA_7") (pintype "bidirectional"))
      (node (ref "S21") (pin "7") (pinfunction "SDA_7") (pintype "bidirectional"))
      (node (ref "S22") (pin "7") (pinfunction "SDA_7") (pintype "bidirectional"))
      (node (ref "S23") (pin "7") (pinfunction "SDA_7") (pintype "bidirectional"))
      (node (ref "S30") (pin "7") (pinfunction "SDA_7") (pintype "bidirectional"))
      (node (ref "S31") (pin "7") (pinfunction "SDA_7") (pintype "bidirectional"))
      (node (ref "S32") (pin "7") (pinfunction "SDA_7") (pintype "bidirectional"))
      (node (ref "S33") (pin "7") (pinfunction "SDA_7") (pintype "bidirectional"))
      (node (ref "S40") (pin "7") (pinfunction "SDA_7") (pintype "bidirectional"))
      (node (ref "S41") (pin "7") (pinfunction "SDA_7") (pintype "bidirectional"))
      (node (ref "S42") (pin "7") (pinfunction "SDA_7") (pintype "bidirectional"))
      (node (ref "S43") (pin "7") (pinfunction "SDA_7") (pintype "bidirectional"))
      (node (ref "UC0") (pin "16") (pinfunction "PA6/MOSI_16") (pintype "bidirectional"))
      (node (ref "UC1") (pin "16") (pinfunction "PA6/MOSI_16") (pintype "bidirectional"))
      (node (ref "UC2") (pin "16") (pinfunction "PA6/MOSI_16") (pintype "bidirectional"))
      (node (ref "UC3") (pin "16") (pinfunction "PA6/MOSI_16") (pintype "bidirectional"))
    )
    (net (code "59") (name "USB+") (class "Default")
      (node (ref "CN1") (pin "D+") (pinfunction "D+_D+") (pintype "bidirectional"))
      (node (ref "IC1") (pin "27") (pinfunction "TXD1/USB+/PD7_27") (pintype "bidirectional"))
    )
    (net (code "60") (name "USB-") (class "Default")
      (node (ref "CN1") (pin "D-") (pinfunction "D-_D-") (pintype "bidirectional"))
      (node (ref "IC1") (pin "26") (pinfunction "RXD1/MISO/USB-/PD6_26") (pintype "bidirectional"))
    )
    (net (code "61") (name "unconnected-(CN1-PadID)") (class "Default")
      (node (ref "CN1") (pin "ID") (pinfunction "ID_ID") (pintype "bidirectional"))
    )
    (net (code "62") (name "unconnected-(IC1-OC0A{slash}PD0-Pad20)") (class "Default")
      (node (ref "IC1") (pin "20") (pinfunction "OC0A/PD0_20") (pintype "bidirectional"))
    )
    (net (code "63") (name "unconnected-(IC1-OC0A{slash}SDA{slash}PE0-Pad28)") (class "Default")
      (node (ref "IC1") (pin "28") (pinfunction "OC0A/SDA/PE0_28") (pintype "bidirectional"))
    )
    (net (code "64") (name "unconnected-(IC1-OC0B{slash}XCK0{slash}PD1-Pad21)") (class "Default")
      (node (ref "IC1") (pin "21") (pinfunction "OC0B/XCK0/PD1_21") (pintype "bidirectional"))
    )
    (net (code "65") (name "unconnected-(IC1-OC0C{slash}RXD0{slash}PD2-Pad22)") (class "Default")
      (node (ref "IC1") (pin "22") (pinfunction "OC0C/RXD0/PD2_22") (pintype "bidirectional"))
    )
    (net (code "66") (name "unconnected-(IC1-OC0D{slash}TXD0{slash}PD3-Pad23)") (class "Default")
      (node (ref "IC1") (pin "23") (pinfunction "OC0D/TXD0/PD3_23") (pintype "bidirectional"))
    )
    (net (code "67") (name "unconnected-(IC1-PA0{slash}ADC0{slash}AREFA-Pad40)") (class "Default")
      (node (ref "IC1") (pin "40") (pinfunction "PA0/ADC0/AREFA_40") (pintype "bidirectional"))
    )
    (net (code "68") (name "unconnected-(IC1-PA1{slash}ADC1-Pad41)") (class "Default")
      (node (ref "IC1") (pin "41") (pinfunction "PA1/ADC1_41") (pintype "bidirectional"))
    )
    (net (code "69") (name "unconnected-(IC1-PA2{slash}ADC2-Pad42)") (class "Default")
      (node (ref "IC1") (pin "42") (pinfunction "PA2/ADC2_42") (pintype "bidirectional"))
    )
    (net (code "70") (name "unconnected-(IC1-PA3{slash}ADC3-Pad43)") (class "Default")
      (node (ref "IC1") (pin "43") (pinfunction "PA3/ADC3_43") (pintype "bidirectional"))
    )
    (net (code "71") (name "unconnected-(IC1-PA4{slash}ADC4-Pad44)") (class "Default")
      (node (ref "IC1") (pin "44") (pinfunction "PA4/ADC4_44") (pintype "bidirectional"))
    )
    (net (code "72") (name "unconnected-(IC1-PA5{slash}ADC5-Pad1)") (class "Default")
      (node (ref "IC1") (pin "1") (pinfunction "PA5/ADC5_1") (pintype "bidirectional"))
    )
    (net (code "73") (name "unconnected-(IC1-PA6{slash}ADC6-Pad2)") (class "Default")
      (node (ref "IC1") (pin "2") (pinfunction "PA6/ADC6_2") (pintype "bidirectional"))
    )
    (net (code "74") (name "unconnected-(IC1-PA7{slash}ADC7-Pad3)") (class "Default")
      (node (ref "IC1") (pin "3") (pinfunction "PA7/ADC7_3") (pintype "bidirectional"))
    )
    (net (code "75") (name "unconnected-(IC1-PB0{slash}ADC8{slash}AREFB-Pad4)") (class "Default")
      (node (ref "IC1") (pin "4") (pinfunction "PB0/ADC8/AREFB_4") (pintype "bidirectional"))
    )
    (net (code "76") (name "unconnected-(IC1-PB1{slash}ADC9-Pad5)") (class "Default")
      (node (ref "IC1") (pin "5") (pinfunction "PB1/ADC9_5") (pintype "bidirectional"))
    )
    (net (code "77") (name "unconnected-(IC1-PB2{slash}ADC10{slash}DAC0-Pad6)") (class "Default")
      (node (ref "IC1") (pin "6") (pinfunction "PB2/ADC10/DAC0_6") (pintype "bidirectional"))
    )
    (net (code "78") (name "unconnected-(IC1-PB3{slash}ADC11{slash}DAC1-Pad7)") (class "Default")
      (node (ref "IC1") (pin "7") (pinfunction "PB3/ADC11/DAC1_7") (pintype "bidirectional"))
    )
    (net (code "79") (name "unconnected-(IC1-PC2{slash}OC0C{slash}RXD0-Pad12)") (class "Default")
      (node (ref "IC1") (pin "12") (pinfunction "PC2/OC0C/RXD0_12") (pintype "bidirectional"))
    )
    (net (code "80") (name "unconnected-(IC1-PC3{slash}OC0D{slash}TXD0-Pad13)") (class "Default")
      (node (ref "IC1") (pin "13") (pinfunction "PC3/OC0D/TXD0_13") (pintype "bidirectional"))
    )
    (net (code "81") (name "unconnected-(IC1-PC4{slash}OC1A{slash}#SS-Pad14)") (class "Default")
      (node (ref "IC1") (pin "14") (pinfunction "PC4/OC1A/#SS_14") (pintype "bidirectional"))
    )
    (net (code "82") (name "unconnected-(IC1-PC5{slash}OC1B{slash}MOSI{slash}XCK1-Pad15)") (class "Default")
      (node (ref "IC1") (pin "15") (pinfunction "PC5/OC1B/MOSI/XCK1_15") (pintype "bidirectional"))
    )
    (net (code "83") (name "unconnected-(IC1-PC6{slash}MISO{slash}RXD1-Pad16)") (class "Default")
      (node (ref "IC1") (pin "16") (pinfunction "PC6/MISO/RXD1_16") (pintype "bidirectional"))
    )
    (net (code "84") (name "unconnected-(IC1-PC7{slash}SCK{slash}TXD1{slash}CLKO{slash}EVO-Pad17)") (class "Default")
      (node (ref "IC1") (pin "17") (pinfunction "PC7/SCK/TXD1/CLKO/EVO_17") (pintype "bidirectional"))
    )
    (net (code "85") (name "unconnected-(IC1-RXD0{slash}OC0C{slash}PE2-Pad32)") (class "Default")
      (node (ref "IC1") (pin "32") (pinfunction "RXD0/OC0C/PE2_32") (pintype "bidirectional"))
    )
    (net (code "86") (name "unconnected-(IC1-SS{slash}PD4-Pad24)") (class "Default")
      (node (ref "IC1") (pin "24") (pinfunction "SS/PD4_24") (pintype "bidirectional"))
    )
    (net (code "87") (name "unconnected-(IC1-TXD0{slash}OC0D{slash}PE3-Pad33)") (class "Default")
      (node (ref "IC1") (pin "33") (pinfunction "TXD0/OC0D/PE3_33") (pintype "bidirectional"))
    )
    (net (code "88") (name "unconnected-(IC1-XCK0{slash}OC0B{slash}SCL{slash}PE1-Pad29)") (class "Default")
      (node (ref "IC1") (pin "29") (pinfunction "XCK0/OC0B/SCL/PE1_29") (pintype "bidirectional"))
    )
    (net (code "89") (name "unconnected-(IC1-XCK1{slash}MOSI{slash}PD5-Pad25)") (class "Default")
      (node (ref "IC1") (pin "25") (pinfunction "XCK1/MOSI/PD5_25") (pintype "bidirectional"))
    )
    (net (code "90") (name "unconnected-(PROG-XMEGA-Pad3)") (class "Default")
      (node (ref "PROG-XMEGA") (pin "3") (pinfunction "3_3") (pintype "passive"))
    )
    (net (code "91") (name "unconnected-(S00-NC-Pad6)") (class "Default")
      (node (ref "S00") (pin "6") (pinfunction "NC_6") (pintype "bidirectional"))
    )
    (net (code "92") (name "unconnected-(S01-NC-Pad6)") (class "Default")
      (node (ref "S01") (pin "6") (pinfunction "NC_6") (pintype "bidirectional"))
    )
    (net (code "93") (name "unconnected-(S02-NC-Pad6)") (class "Default")
      (node (ref "S02") (pin "6") (pinfunction "NC_6") (pintype "bidirectional"))
    )
    (net (code "94") (name "unconnected-(S03-NC-Pad6)") (class "Default")
      (node (ref "S03") (pin "6") (pinfunction "NC_6") (pintype "bidirectional"))
    )
    (net (code "95") (name "unconnected-(S10-NC-Pad6)") (class "Default")
      (node (ref "S10") (pin "6") (pinfunction "NC_6") (pintype "bidirectional"))
    )
    (net (code "96") (name "unconnected-(S11-NC-Pad6)") (class "Default")
      (node (ref "S11") (pin "6") (pinfunction "NC_6") (pintype "bidirectional"))
    )
    (net (code "97") (name "unconnected-(S12-NC-Pad6)") (class "Default")
      (node (ref "S12") (pin "6") (pinfunction "NC_6") (pintype "bidirectional"))
    )
    (net (code "98") (name "unconnected-(S13-NC-Pad6)") (class "Default")
      (node (ref "S13") (pin "6") (pinfunction "NC_6") (pintype "bidirectional"))
    )
    (net (code "99") (name "unconnected-(S20-NC-Pad6)") (class "Default")
      (node (ref "S20") (pin "6") (pinfunction "NC_6") (pintype "bidirectional"))
    )
    (net (code "100") (name "unconnected-(S21-NC-Pad6)") (class "Default")
      (node (ref "S21") (pin "6") (pinfunction "NC_6") (pintype "bidirectional"))
    )
    (net (code "101") (name "unconnected-(S22-NC-Pad6)") (class "Default")
      (node (ref "S22") (pin "6") (pinfunction "NC_6") (pintype "bidirectional"))
    )
    (net (code "102") (name "unconnected-(S23-NC-Pad6)") (class "Default")
      (node (ref "S23") (pin "6") (pinfunction "NC_6") (pintype "bidirectional"))
    )
    (net (code "103") (name "unconnected-(S30-NC-Pad6)") (class "Default")
      (node (ref "S30") (pin "6") (pinfunction "NC_6") (pintype "bidirectional"))
    )
    (net (code "104") (name "unconnected-(S31-NC-Pad6)") (class "Default")
      (node (ref "S31") (pin "6") (pinfunction "NC_6") (pintype "bidirectional"))
    )
    (net (code "105") (name "unconnected-(S32-NC-Pad6)") (class "Default")
      (node (ref "S32") (pin "6") (pinfunction "NC_6") (pintype "bidirectional"))
    )
    (net (code "106") (name "unconnected-(S33-NC-Pad6)") (class "Default")
      (node (ref "S33") (pin "6") (pinfunction "NC_6") (pintype "bidirectional"))
    )
    (net (code "107") (name "unconnected-(S40-NC-Pad6)") (class "Default")
      (node (ref "S40") (pin "6") (pinfunction "NC_6") (pintype "bidirectional"))
    )
    (net (code "108") (name "unconnected-(S41-NC-Pad6)") (class "Default")
      (node (ref "S41") (pin "6") (pinfunction "NC_6") (pintype "bidirectional"))
    )
    (net (code "109") (name "unconnected-(S42-NC-Pad6)") (class "Default")
      (node (ref "S42") (pin "6") (pinfunction "NC_6") (pintype "bidirectional"))
    )
    (net (code "110") (name "unconnected-(S43-NC-Pad6)") (class "Default")
      (node (ref "S43") (pin "6") (pinfunction "NC_6") (pintype "bidirectional"))
    )
  )
)
